# test_brd.net
KiCad netlist of a schematic drawn in EAGLE
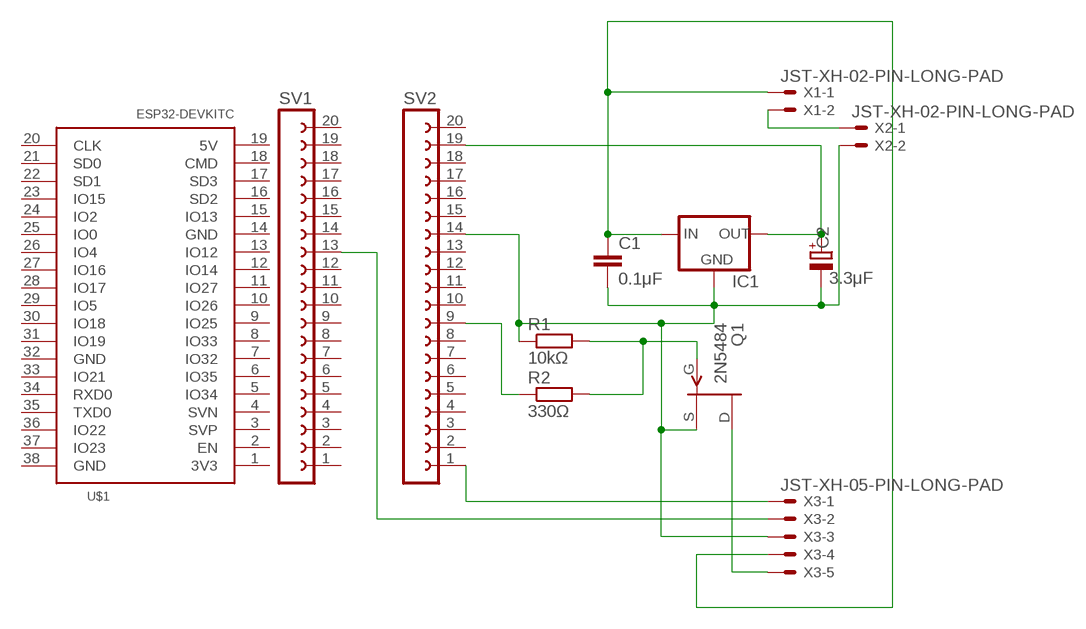
[diagram p0: schematic, sheet 1]

(export (version "E")
  (design (tool "Eeschema 10.0.6"))
  (components
    (comp (ref "C1")
      (value "0.1μF")
      (footprint "eagle-import:C025-040X050")
      (libsource (lib "eagle-import") (part "C-EU025-040X050"))
    )
    (comp (ref "C2")
      (value "3.3μF")
      (footprint "eagle-import:E2,5-5")
      (libsource (lib "eagle-import") (part "CPOL-EUE2.5-5"))
    )
    (comp (ref "IC1")
      (value "78XXS")
      (footprint "eagle-import:78XXS")
      (libsource (lib "eagle-import") (part "78XXS"))
    )
    (comp (ref "Q1")
      (value "2N5484")
      (footprint "eagle-import:TO92-")
      (libsource (lib "eagle-import") (part "?5482N4"))
    )
    (comp (ref "R1")
      (value "10kΩ")
      (footprint "eagle-import:0207_10")
      (libsource (lib "eagle-import") (part "R-EU_0207/10"))
    )
    (comp (ref "R2")
      (value "330Ω")
      (footprint "eagle-import:0207_10")
      (libsource (lib "eagle-import") (part "R-EU_0207/10"))
    )
    (comp (ref "SV1")
      (value "FE20-1")
      (footprint "eagle-import:FE20")
      (libsource (lib "eagle-import") (part "FE20-1"))
    )
    (comp (ref "SV2")
      (value "FE20-1")
      (footprint "eagle-import:FE20")
      (libsource (lib "eagle-import") (part "FE20-1"))
    )
    (comp (ref "U$1")
      (value "ESP32DEVKITC")
      (footprint "eagle-import:ESP32-DEVKITC")
      (libsource (lib "eagle-import") (part "ESP32DEVKITC"))
    )
    (comp (ref "X1")
      (value "JST-XH-02-PIN-LONG-PAD")
      (footprint "eagle-import:JST-XH-02-PACKAGE-LONG-PAD")
      (libsource (lib "eagle-import") (part "JST-XH-02-PIN-LONG-PAD"))
    )
    (comp (ref "X2")
      (value "JST-XH-02-PIN-LONG-PAD")
      (footprint "eagle-import:JST-XH-02-PACKAGE-LONG-PAD")
      (libsource (lib "eagle-import") (part "JST-XH-02-PIN-LONG-PAD"))
    )
    (comp (ref "X3")
      (value "JST-XH-05-PIN-LONG-PAD")
      (footprint "eagle-import:JST-XH-05-PACKAGE-LONG-PAD")
      (libsource (lib "eagle-import") (part "JST-XH-05-PIN-LONG-PAD"))
    )
  )
  (nets
    (net (code "1") (name "Net-(C2-Pad+)") (class "Default")
      (node (ref "C2") (pin "+") (pinfunction "+_+") (pintype "passive"))
      (node (ref "IC1") (pin "OUT") (pinfunction "OUT_OUT") (pintype "passive"))
      (node (ref "SV2") (pin "19") (pinfunction "19_19") (pintype "passive"))
    )
    (net (code "2") (name "Net-(Q1-D)") (class "Default")
      (node (ref "Q1") (pin "3") (pinfunction "D_3") (pintype "passive"))
      (node (ref "X3") (pin "5") (pinfunction "S_5") (pintype "passive"))
    )
    (net (code "3") (name "Net-(Q1-G)") (class "Default")
      (node (ref "Q1") (pin "1") (pinfunction "G_1") (pintype "passive"))
      (node (ref "R1") (pin "2") (pinfunction "2_2") (pintype "passive"))
      (node (ref "R2") (pin "2") (pinfunction "2_2") (pintype "passive"))
    )
    (net (code "4") (name "Net-(Q1-S)") (class "Default")
      (node (ref "C1") (pin "2") (pinfunction "2_2") (pintype "passive"))
      (node (ref "C2") (pin "-") (pinfunction "-_-") (pintype "passive"))
      (node (ref "IC1") (pin "GND") (pinfunction "GND_GND") (pintype "input"))
      (node (ref "Q1") (pin "2") (pinfunction "S_2") (pintype "passive"))
      (node (ref "R1") (pin "1") (pinfunction "1_1") (pintype "passive"))
      (node (ref "SV2") (pin "14") (pinfunction "14_14") (pintype "passive"))
      (node (ref "X2") (pin "2") (pinfunction "S_2") (pintype "passive"))
      (node (ref "X3") (pin "3") (pinfunction "S_3") (pintype "passive"))
    )
    (net (code "5") (name "Net-(R2-Pad1)") (class "Default")
      (node (ref "R2") (pin "1") (pinfunction "1_1") (pintype "passive"))
      (node (ref "SV2") (pin "9") (pinfunction "9_9") (pintype "passive"))
    )
    (net (code "6") (name "Net-(X1A-S)") (class "Default")
      (node (ref "C1") (pin "1") (pinfunction "1_1") (pintype "passive"))
      (node (ref "IC1") (pin "IN") (pinfunction "IN_IN") (pintype "input"))
      (node (ref "X1") (pin "1") (pinfunction "S_1") (pintype "passive"))
      (node (ref "X3") (pin "4") (pinfunction "S_4") (pintype "passive"))
    )
    (net (code "7") (name "Net-(X1B-S)") (class "Default")
      (node (ref "X1") (pin "2") (pinfunction "S_2") (pintype "passive"))
      (node (ref "X2") (pin "1") (pinfunction "S_1") (pintype "passive"))
    )
    (net (code "8") (name "Net-(X3A-S)") (class "Default")
      (node (ref "SV2") (pin "1") (pinfunction "1_1") (pintype "passive"))
      (node (ref "X3") (pin "1") (pinfunction "S_1") (pintype "passive"))
    )
    (net (code "9") (name "Net-(X3B-S)") (class "Default")
      (node (ref "SV1") (pin "13") (pinfunction "13_13") (pintype "passive"))
      (node (ref "X3") (pin "2") (pinfunction "S_2") (pintype "passive"))
    )
    (net (code "10") (name "unconnected-(SV1-Pad1)") (class "Default")
      (node (ref "SV1") (pin "1") (pinfunction "1_1") (pintype "passive"))
    )
    (net (code "11") (name "unconnected-(SV1-Pad2)") (class "Default")
      (node (ref "SV1") (pin "2") (pinfunction "2_2") (pintype "passive"))
    )
    (net (code "12") (name "unconnected-(SV1-Pad3)") (class "Default")
      (node (ref "SV1") (pin "3") (pinfunction "3_3") (pintype "passive"))
    )
    (net (code "13") (name "unconnected-(SV1-Pad4)") (class "Default")
      (node (ref "SV1") (pin "4") (pinfunction "4_4") (pintype "passive"))
    )
    (net (code "14") (name "unconnected-(SV1-Pad5)") (class "Default")
      (node (ref "SV1") (pin "5") (pinfunction "5_5") (pintype "passive"))
    )
    (net (code "15") (name "unconnected-(SV1-Pad6)") (class "Default")
      (node (ref "SV1") (pin "6") (pinfunction "6_6") (pintype "passive"))
    )
    (net (code "16") (name "unconnected-(SV1-Pad7)") (class "Default")
      (node (ref "SV1") (pin "7") (pinfunction "7_7") (pintype "passive"))
    )
    (net (code "17") (name "unconnected-(SV1-Pad8)") (class "Default")
      (node (ref "SV1") (pin "8") (pinfunction "8_8") (pintype "passive"))
    )
    (net (code "18") (name "unconnected-(SV1-Pad9)") (class "Default")
      (node (ref "SV1") (pin "9") (pinfunction "9_9") (pintype "passive"))
    )
    (net (code "19") (name "unconnected-(SV1-Pad10)") (class "Default")
      (node (ref "SV1") (pin "10") (pinfunction "10_10") (pintype "passive"))
    )
    (net (code "20") (name "unconnected-(SV1-Pad11)") (class "Default")
      (node (ref "SV1") (pin "11") (pinfunction "11_11") (pintype "passive"))
    )
    (net (code "21") (name "unconnected-(SV1-Pad12)") (class "Default")
      (node (ref "SV1") (pin "12") (pinfunction "12_12") (pintype "passive"))
    )
    (net (code "22") (name "unconnected-(SV1-Pad14)") (class "Default")
      (node (ref "SV1") (pin "14") (pinfunction "14_14") (pintype "passive"))
    )
    (net (code "23") (name "unconnected-(SV1-Pad15)") (class "Default")
      (node (ref "SV1") (pin "15") (pinfunction "15_15") (pintype "passive"))
    )
    (net (code "24") (name "unconnected-(SV1-Pad16)") (class "Default")
      (node (ref "SV1") (pin "16") (pinfunction "16_16") (pintype "passive"))
    )
    (net (code "25") (name "unconnected-(SV1-Pad17)") (class "Default")
      (node (ref "SV1") (pin "17") (pinfunction "17_17") (pintype "passive"))
    )
    (net (code "26") (name "unconnected-(SV1-Pad18)") (class "Default")
      (node (ref "SV1") (pin "18") (pinfunction "18_18") (pintype "passive"))
    )
    (net (code "27") (name "unconnected-(SV1-Pad19)") (class "Default")
      (node (ref "SV1") (pin "19") (pinfunction "19_19") (pintype "passive"))
    )
    (net (code "28") (name "unconnected-(SV1-Pad20)") (class "Default")
      (node (ref "SV1") (pin "20") (pinfunction "20_20") (pintype "passive"))
    )
    (net (code "29") (name "unconnected-(SV2-Pad2)") (class "Default")
      (node (ref "SV2") (pin "2") (pinfunction "2_2") (pintype "passive"))
    )
    (net (code "30") (name "unconnected-(SV2-Pad3)") (class "Default")
      (node (ref "SV2") (pin "3") (pinfunction "3_3") (pintype "passive"))
    )
    (net (code "31") (name "unconnected-(SV2-Pad4)") (class "Default")
      (node (ref "SV2") (pin "4") (pinfunction "4_4") (pintype "passive"))
    )
    (net (code "32") (name "unconnected-(SV2-Pad5)") (class "Default")
      (node (ref "SV2") (pin "5") (pinfunction "5_5") (pintype "passive"))
    )
    (net (code "33") (name "unconnected-(SV2-Pad6)") (class "Default")
      (node (ref "SV2") (pin "6") (pinfunction "6_6") (pintype "passive"))
    )
    (net (code "34") (name "unconnected-(SV2-Pad7)") (class "Default")
      (node (ref "SV2") (pin "7") (pinfunction "7_7") (pintype "passive"))
    )
    (net (code "35") (name "unconnected-(SV2-Pad8)") (class "Default")
      (node (ref "SV2") (pin "8") (pinfunction "8_8") (pintype "passive"))
    )
    (net (code "36") (name "unconnected-(SV2-Pad10)") (class "Default")
      (node (ref "SV2") (pin "10") (pinfunction "10_10") (pintype "passive"))
    )
    (net (code "37") (name "unconnected-(SV2-Pad11)") (class "Default")
      (node (ref "SV2") (pin "11") (pinfunction "11_11") (pintype "passive"))
    )
    (net (code "38") (name "unconnected-(SV2-Pad12)") (class "Default")
      (node (ref "SV2") (pin "12") (pinfunction "12_12") (pintype "passive"))
    )
    (net (code "39") (name "unconnected-(SV2-Pad13)") (class "Default")
      (node (ref "SV2") (pin "13") (pinfunction "13_13") (pintype "passive"))
    )
    (net (code "40") (name "unconnected-(SV2-Pad15)") (class "Default")
      (node (ref "SV2") (pin "15") (pinfunction "15_15") (pintype "passive"))
    )
    (net (code "41") (name "unconnected-(SV2-Pad16)") (class "Default")
      (node (ref "SV2") (pin "16") (pinfunction "16_16") (pintype "passive"))
    )
    (net (code "42") (name "unconnected-(SV2-Pad17)") (class "Default")
      (node (ref "SV2") (pin "17") (pinfunction "17_17") (pintype "passive"))
    )
    (net (code "43") (name "unconnected-(SV2-Pad18)") (class "Default")
      (node (ref "SV2") (pin "18") (pinfunction "18_18") (pintype "passive"))
    )
    (net (code "44") (name "unconnected-(SV2-Pad20)") (class "Default")
      (node (ref "SV2") (pin "20") (pinfunction "20_20") (pintype "passive"))
    )
    (net (code "45") (name "unconnected-(U$1-3V3-Pad1)") (class "Default")
      (node (ref "U$1") (pin "1") (pinfunction "3V3_1") (pintype "bidirectional"))
    )
    (net (code "46") (name "unconnected-(U$1-5V-Pad19)") (class "Default")
      (node (ref "U$1") (pin "19") (pinfunction "5V_19") (pintype "bidirectional"))
    )
    (net (code "47") (name "unconnected-(U$1-CLK-Pad20)") (class "Default")
      (node (ref "U$1") (pin "20") (pinfunction "CLK_20") (pintype "bidirectional"))
    )
    (net (code "48") (name "unconnected-(U$1-CMD-Pad18)") (class "Default")
      (node (ref "U$1") (pin "18") (pinfunction "CMD_18") (pintype "bidirectional"))
    )
    (net (code "49") (name "unconnected-(U$1-EN-Pad2)") (class "Default")
      (node (ref "U$1") (pin "2") (pinfunction "EN_2") (pintype "bidirectional"))
    )
    (net (code "50") (name "unconnected-(U$1-GND-Pad14)") (class "Default")
      (node (ref "U$1") (pin "14") (pinfunction "GND_14") (pintype "bidirectional"))
    )
    (net (code "51") (name "unconnected-(U$1-GND-Pad32)") (class "Default")
      (node (ref "U$1") (pin "32") (pinfunction "GND_32") (pintype "bidirectional"))
    )
    (net (code "52") (name "unconnected-(U$1-GND-Pad38)") (class "Default")
      (node (ref "U$1") (pin "38") (pinfunction "GND_38") (pintype "bidirectional"))
    )
    (net (code "53") (name "unconnected-(U$1-IO0-Pad25)") (class "Default")
      (node (ref "U$1") (pin "25") (pinfunction "IO0_25") (pintype "bidirectional"))
    )
    (net (code "54") (name "unconnected-(U$1-IO2-Pad24)") (class "Default")
      (node (ref "U$1") (pin "24") (pinfunction "IO2_24") (pintype "bidirectional"))
    )
    (net (code "55") (name "unconnected-(U$1-IO4-Pad26)") (class "Default")
      (node (ref "U$1") (pin "26") (pinfunction "IO4_26") (pintype "bidirectional"))
    )
    (net (code "56") (name "unconnected-(U$1-IO5-Pad29)") (class "Default")
      (node (ref "U$1") (pin "29") (pinfunction "IO5_29") (pintype "bidirectional"))
    )
    (net (code "57") (name "unconnected-(U$1-IO12-Pad13)") (class "Default")
      (node (ref "U$1") (pin "13") (pinfunction "IO12_13") (pintype "bidirectional"))
    )
    (net (code "58") (name "unconnected-(U$1-IO13-Pad15)") (class "Default")
      (node (ref "U$1") (pin "15") (pinfunction "IO13_15") (pintype "bidirectional"))
    )
    (net (code "59") (name "unconnected-(U$1-IO14-Pad12)") (class "Default")
      (node (ref "U$1") (pin "12") (pinfunction "IO14_12") (pintype "bidirectional"))
    )
    (net (code "60") (name "unconnected-(U$1-IO15-Pad23)") (class "Default")
      (node (ref "U$1") (pin "23") (pinfunction "IO15_23") (pintype "bidirectional"))
    )
    (net (code "61") (name "unconnected-(U$1-IO16-Pad27)") (class "Default")
      (node (ref "U$1") (pin "27") (pinfunction "IO16_27") (pintype "bidirectional"))
    )
    (net (code "62") (name "unconnected-(U$1-IO17-Pad28)") (class "Default")
      (node (ref "U$1") (pin "28") (pinfunction "IO17_28") (pintype "bidirectional"))
    )
    (net (code "63") (name "unconnected-(U$1-IO18-Pad30)") (class "Default")
      (node (ref "U$1") (pin "30") (pinfunction "IO18_30") (pintype "bidirectional"))
    )
    (net (code "64") (name "unconnected-(U$1-IO19-Pad31)") (class "Default")
      (node (ref "U$1") (pin "31") (pinfunction "IO19_31") (pintype "bidirectional"))
    )
    (net (code "65") (name "unconnected-(U$1-IO21-Pad33)") (class "Default")
      (node (ref "U$1") (pin "33") (pinfunction "IO21_33") (pintype "bidirectional"))
    )
    (net (code "66") (name "unconnected-(U$1-IO22-Pad36)") (class "Default")
      (node (ref "U$1") (pin "36") (pinfunction "IO22_36") (pintype "bidirectional"))
    )
    (net (code "67") (name "unconnected-(U$1-IO23-Pad37)") (class "Default")
      (node (ref "U$1") (pin "37") (pinfunction "IO23_37") (pintype "bidirectional"))
    )
    (net (code "68") (name "unconnected-(U$1-IO25-Pad9)") (class "Default")
      (node (ref "U$1") (pin "9") (pinfunction "IO25_9") (pintype "bidirectional"))
    )
    (net (code "69") (name "unconnected-(U$1-IO26-Pad10)") (class "Default")
      (node (ref "U$1") (pin "10") (pinfunction "IO26_10") (pintype "bidirectional"))
    )
    (net (code "70") (name "unconnected-(U$1-IO27-Pad11)") (class "Default")
      (node (ref "U$1") (pin "11") (pinfunction "IO27_11") (pintype "bidirectional"))
    )
    (net (code "71") (name "unconnected-(U$1-IO32-Pad7)") (class "Default")
      (node (ref "U$1") (pin "7") (pinfunction "IO32_7") (pintype "bidirectional"))
    )
    (net (code "72") (name "unconnected-(U$1-IO33-Pad8)") (class "Default")
      (node (ref "U$1") (pin "8") (pinfunction "IO33_8") (pintype "bidirectional"))
    )
    (net (code "73") (name "unconnected-(U$1-IO34-Pad5)") (class "Default")
      (node (ref "U$1") (pin "5") (pinfunction "IO34_5") (pintype "bidirectional"))
    )
    (net (code "74") (name "unconnected-(U$1-IO35-Pad6)") (class "Default")
      (node (ref "U$1") (pin "6") (pinfunction "IO35_6") (pintype "bidirectional"))
    )
    (net (code "75") (name "unconnected-(U$1-RXD0-Pad34)") (class "Default")
      (node (ref "U$1") (pin "34") (pinfunction "RXD0_34") (pintype "bidirectional"))
    )
    (net (code "76") (name "unconnected-(U$1-SD0-Pad21)") (class "Default")
      (node (ref "U$1") (pin "21") (pinfunction "SD0_21") (pintype "bidirectional"))
    )
    (net (code "77") (name "unconnected-(U$1-SD1-Pad22)") (class "Default")
      (node (ref "U$1") (pin "22") (pinfunction "SD1_22") (pintype "bidirectional"))
    )
    (net (code "78") (name "unconnected-(U$1-SD2-Pad16)") (class "Default")
      (node (ref "U$1") (pin "16") (pinfunction "SD2_16") (pintype "bidirectional"))
    )
    (net (code "79") (name "unconnected-(U$1-SD3-Pad17)") (class "Default")
      (node (ref "U$1") (pin "17") (pinfunction "SD3_17") (pintype "bidirectional"))
    )
    (net (code "80") (name "unconnected-(U$1-SVN-Pad4)") (class "Default")
      (node (ref "U$1") (pin "4") (pinfunction "SVN_4") (pintype "bidirectional"))
    )
    (net (code "81") (name "unconnected-(U$1-SVP-Pad3)") (class "Default")
      (node (ref "U$1") (pin "3") (pinfunction "SVP_3") (pintype "bidirectional"))
    )
    (net (code "82") (name "unconnected-(U$1-TXD0-Pad35)") (class "Default")
      (node (ref "U$1") (pin "35") (pinfunction "TXD0_35") (pintype "bidirectional"))
    )
  )
)
